# pulse_iot.net
KiCad netlist of a schematic drawn in EAGLE
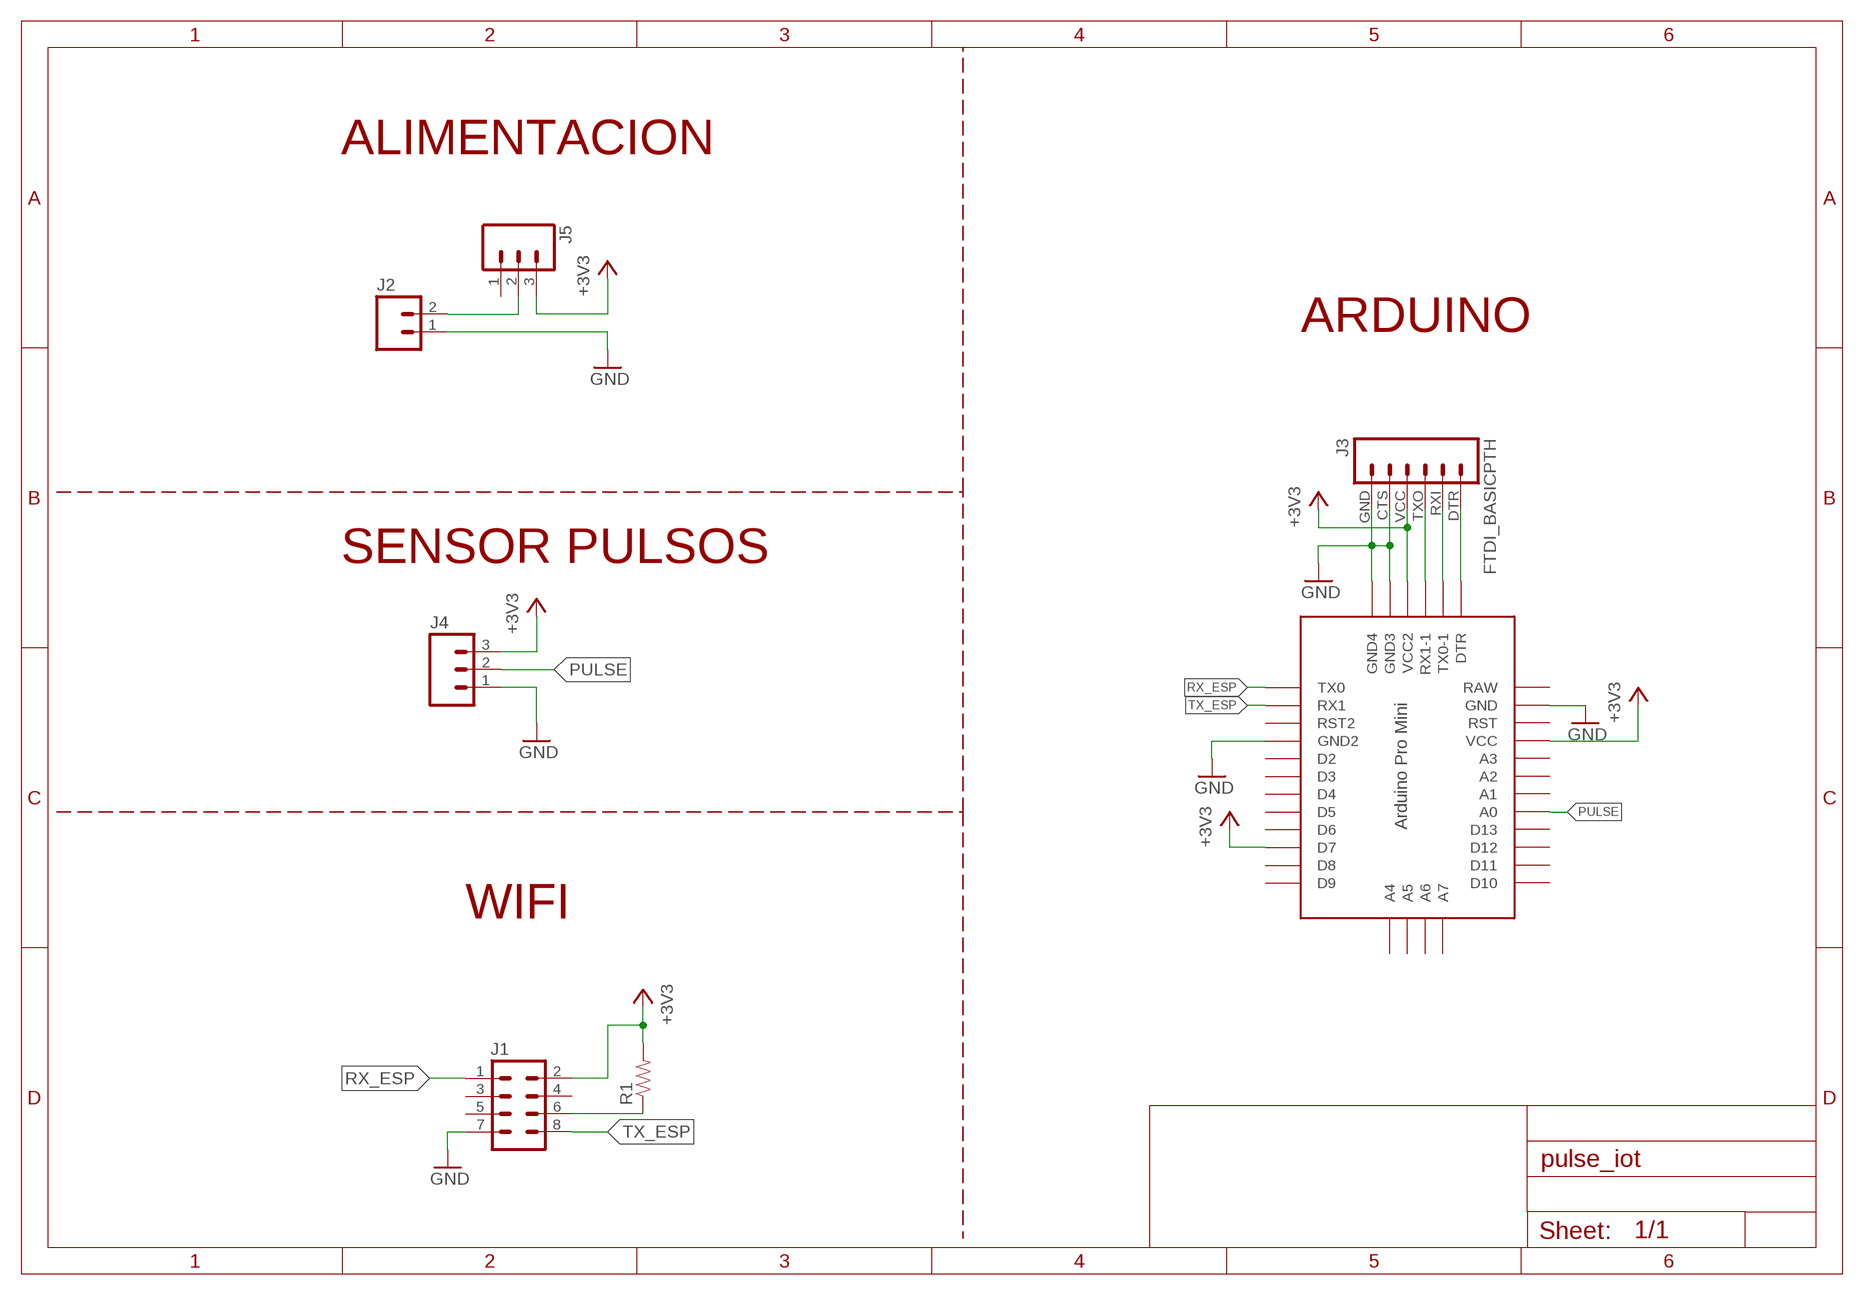
[diagram p0: schematic, sheet 1]

(export (version "E")
  (design (tool "Eeschema 10.0.6"))
  (components
    (comp (ref "J1")
      (value "M04X2")
      (footprint "eagle-import:2X4")
      (libsource (lib "eagle-import") (part "M04X2"))
    )
    (comp (ref "J2")
      (value "M025MM")
      (footprint "eagle-import:SCREWTERMINAL-5MM-2")
      (libsource (lib "eagle-import") (part "M025MM"))
    )
    (comp (ref "J3")
      (value "FTDI_BASICPTH")
      (footprint "eagle-import:FTDI_BASIC")
      (libsource (lib "eagle-import") (part "FTDI_BASICPTH"))
    )
    (comp (ref "J4")
      (value "M03-SCREW-5MM")
      (footprint "eagle-import:SCREWTERMINAL-5MM-3")
      (libsource (lib "eagle-import") (part "M03-SCREW-5MM"))
    )
    (comp (ref "J5")
      (value "M03LONGPADS")
      (footprint "eagle-import:1X03_LONGPADS")
      (libsource (lib "eagle-import") (part "M03LONGPADS"))
    )
    (comp (ref "R1")
      (value "RESISTORPTH1")
      (footprint "eagle-import:AXIAL-0.3")
      (libsource (lib "eagle-import") (part "RESISTORPTH1"))
    )
    (comp (ref "U$1")
      (value "PRO-MINI")
      (footprint "eagle-import:PRO-MINI")
      (libsource (lib "eagle-import") (part "PRO-MINI"))
    )
  )
  (nets
    (net (code "1") (name "+3V3") (class "Default")
      (node (ref "J1") (pin "2") (pinfunction "2_2") (pintype "passive"))
      (node (ref "J3") (pin "VCC") (pinfunction "4_VCC") (pintype "passive"))
      (node (ref "J4") (pin "3") (pinfunction "3_3") (pintype "passive"))
      (node (ref "J5") (pin "3") (pinfunction "3_3") (pintype "passive"))
      (node (ref "R1") (pin "P$2") (pinfunction "2_P$2") (pintype "passive"))
      (node (ref "U$1") (pin "D7") (pinfunction "D7_D7") (pintype "bidirectional"))
      (node (ref "U$1") (pin "VCC") (pinfunction "VCC_VCC") (pintype "bidirectional"))
      (node (ref "U$1") (pin "VCC1") (pinfunction "VCC2_VCC1") (pintype "bidirectional"))
    )
    (net (code "2") (name "/RAW") (class "Default")
      (node (ref "U$1") (pin "RAW") (pinfunction "RAW_RAW") (pintype "power_in"))
    )
    (net (code "3") (name "GND") (class "Default")
      (node (ref "J1") (pin "7") (pinfunction "7_7") (pintype "passive"))
      (node (ref "J2") (pin "1") (pinfunction "1_1") (pintype "passive"))
      (node (ref "J3") (pin "CTS") (pinfunction "5_CTS") (pintype "passive"))
      (node (ref "J3") (pin "GND") (pinfunction "6_GND") (pintype "passive"))
      (node (ref "J4") (pin "1") (pinfunction "1_1") (pintype "passive"))
      (node (ref "U$1") (pin "GND") (pinfunction "GND_GND") (pintype "input"))
      (node (ref "U$1") (pin "GND1") (pinfunction "GND2_GND1") (pintype "bidirectional"))
      (node (ref "U$1") (pin "GND2") (pinfunction "GND4_GND2") (pintype "bidirectional"))
      (node (ref "U$1") (pin "GND3") (pinfunction "GND3_GND3") (pintype "bidirectional"))
    )
    (net (code "4") (name "Net-(J2-Pad2)") (class "Default")
      (node (ref "J2") (pin "2") (pinfunction "2_2") (pintype "passive"))
      (node (ref "J5") (pin "2") (pinfunction "2_2") (pintype "passive"))
    )
    (net (code "5") (name "Net-(J3-1)") (class "Default")
      (node (ref "J3") (pin "DTR") (pinfunction "1_DTR") (pintype "passive"))
      (node (ref "U$1") (pin "DTR") (pinfunction "DTR_DTR") (pintype "bidirectional"))
    )
    (net (code "6") (name "Net-(J3-2)") (class "Default")
      (node (ref "J3") (pin "RXI") (pinfunction "2_RXI") (pintype "passive"))
      (node (ref "U$1") (pin "TX0-1") (pinfunction "TX0-1_TX0-1") (pintype "bidirectional"))
    )
    (net (code "7") (name "Net-(J3-3)") (class "Default")
      (node (ref "J3") (pin "TXO") (pinfunction "3_TXO") (pintype "passive"))
      (node (ref "U$1") (pin "RX1-1") (pinfunction "RX1-1_RX1-1") (pintype "bidirectional"))
    )
    (net (code "8") (name "Net-(R1-1)") (class "Default")
      (node (ref "J1") (pin "6") (pinfunction "6_6") (pintype "passive"))
      (node (ref "R1") (pin "P$1") (pinfunction "1_P$1") (pintype "passive"))
    )
    (net (code "9") (name "PULSE") (class "Default")
      (node (ref "J4") (pin "2") (pinfunction "2_2") (pintype "passive"))
      (node (ref "U$1") (pin "A0") (pinfunction "A0_A0") (pintype "bidirectional"))
    )
    (net (code "10") (name "RX_ESP") (class "Default")
      (node (ref "J1") (pin "1") (pinfunction "1_1") (pintype "passive"))
      (node (ref "U$1") (pin "TX0") (pinfunction "TX0_TX0") (pintype "bidirectional"))
    )
    (net (code "11") (name "TX_ESP") (class "Default")
      (node (ref "J1") (pin "8") (pinfunction "8_8") (pintype "passive"))
      (node (ref "U$1") (pin "RX1") (pinfunction "RX1_RX1") (pintype "bidirectional"))
    )
    (net (code "12") (name "unconnected-(J1-Pad3)") (class "Default")
      (node (ref "J1") (pin "3") (pinfunction "3_3") (pintype "passive"))
    )
    (net (code "13") (name "unconnected-(J1-Pad4)") (class "Default")
      (node (ref "J1") (pin "4") (pinfunction "4_4") (pintype "passive"))
    )
    (net (code "14") (name "unconnected-(J1-Pad5)") (class "Default")
      (node (ref "J1") (pin "5") (pinfunction "5_5") (pintype "passive"))
    )
    (net (code "15") (name "unconnected-(J5-Pad1)") (class "Default")
      (node (ref "J5") (pin "1") (pinfunction "1_1") (pintype "passive"))
    )
    (net (code "16") (name "unconnected-(U$1-PadA1)") (class "Default")
      (node (ref "U$1") (pin "A1") (pinfunction "A1_A1") (pintype "bidirectional"))
    )
    (net (code "17") (name "unconnected-(U$1-PadA2)") (class "Default")
      (node (ref "U$1") (pin "A2") (pinfunction "A2_A2") (pintype "bidirectional"))
    )
    (net (code "18") (name "unconnected-(U$1-PadA3)") (class "Default")
      (node (ref "U$1") (pin "A3") (pinfunction "A3_A3") (pintype "bidirectional"))
    )
    (net (code "19") (name "unconnected-(U$1-PadA4)") (class "Default")
      (node (ref "U$1") (pin "A4") (pinfunction "A4_A4") (pintype "bidirectional"))
    )
    (net (code "20") (name "unconnected-(U$1-PadA5)") (class "Default")
      (node (ref "U$1") (pin "A5") (pinfunction "A5_A5") (pintype "bidirectional"))
    )
    (net (code "21") (name "unconnected-(U$1-PadA6)") (class "Default")
      (node (ref "U$1") (pin "A6") (pinfunction "A6_A6") (pintype "bidirectional"))
    )
    (net (code "22") (name "unconnected-(U$1-PadA7)") (class "Default")
      (node (ref "U$1") (pin "A7") (pinfunction "A7_A7") (pintype "bidirectional"))
    )
    (net (code "23") (name "unconnected-(U$1-PadD2)") (class "Default")
      (node (ref "U$1") (pin "D2") (pinfunction "D2_D2") (pintype "bidirectional"))
    )
    (net (code "24") (name "unconnected-(U$1-PadD3)") (class "Default")
      (node (ref "U$1") (pin "D3") (pinfunction "D3_D3") (pintype "bidirectional"))
    )
    (net (code "25") (name "unconnected-(U$1-PadD4)") (class "Default")
      (node (ref "U$1") (pin "D4") (pinfunction "D4_D4") (pintype "bidirectional"))
    )
    (net (code "26") (name "unconnected-(U$1-PadD5)") (class "Default")
      (node (ref "U$1") (pin "D5") (pinfunction "D5_D5") (pintype "bidirectional"))
    )
    (net (code "27") (name "unconnected-(U$1-PadD6)") (class "Default")
      (node (ref "U$1") (pin "D6") (pinfunction "D6_D6") (pintype "bidirectional"))
    )
    (net (code "28") (name "unconnected-(U$1-PadD8)") (class "Default")
      (node (ref "U$1") (pin "D8") (pinfunction "D8_D8") (pintype "bidirectional"))
    )
    (net (code "29") (name "unconnected-(U$1-PadD9)") (class "Default")
      (node (ref "U$1") (pin "D9") (pinfunction "D9_D9") (pintype "bidirectional"))
    )
    (net (code "30") (name "unconnected-(U$1-PadD10)") (class "Default")
      (node (ref "U$1") (pin "D10") (pinfunction "D10_D10") (pintype "bidirectional"))
    )
    (net (code "31") (name "unconnected-(U$1-PadD11)") (class "Default")
      (node (ref "U$1") (pin "D11") (pinfunction "D11_D11") (pintype "bidirectional"))
    )
    (net (code "32") (name "unconnected-(U$1-PadD12)") (class "Default")
      (node (ref "U$1") (pin "D12") (pinfunction "D12_D12") (pintype "bidirectional"))
    )
    (net (code "33") (name "unconnected-(U$1-PadD13)") (class "Default")
      (node (ref "U$1") (pin "D13") (pinfunction "D13_D13") (pintype "bidirectional"))
    )
    (net (code "34") (name "unconnected-(U$1-PadRST)") (class "Default")
      (node (ref "U$1") (pin "RST") (pinfunction "RST_RST") (pintype "bidirectional"))
    )
    (net (code "35") (name "unconnected-(U$1-RST2-PadRST1)") (class "Default")
      (node (ref "U$1") (pin "RST1") (pinfunction "RST2_RST1") (pintype "bidirectional"))
    )
  )
)
